# controller5.net
KiCad netlist of a schematic drawn in EAGLE
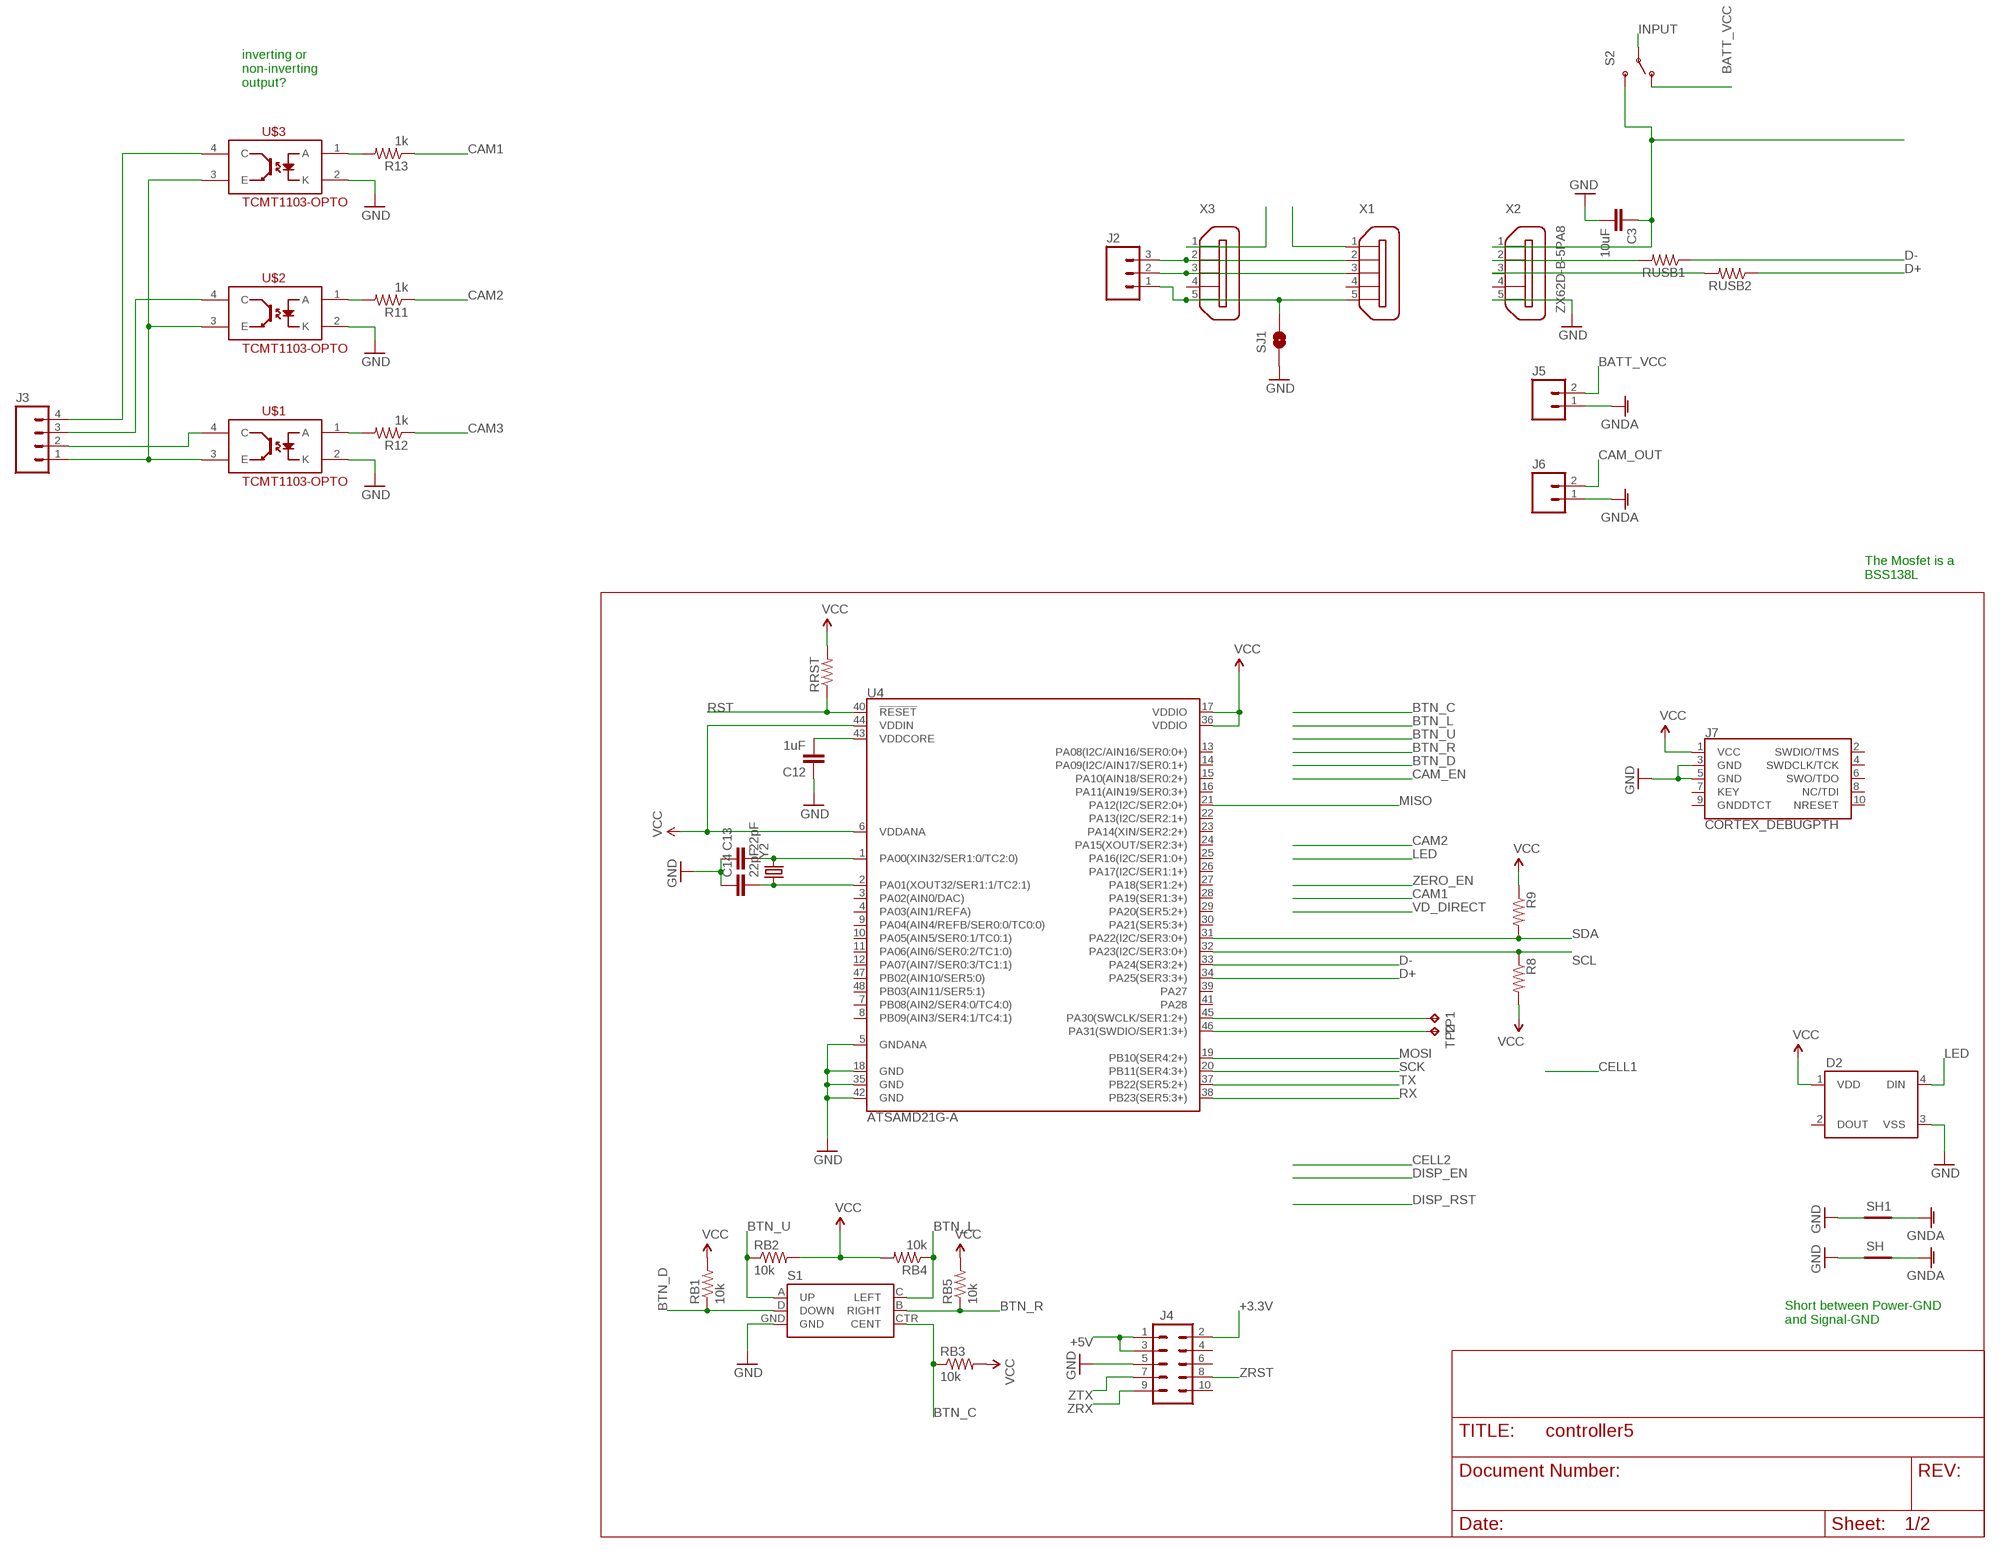
[diagram p0: schematic, sheet 1]
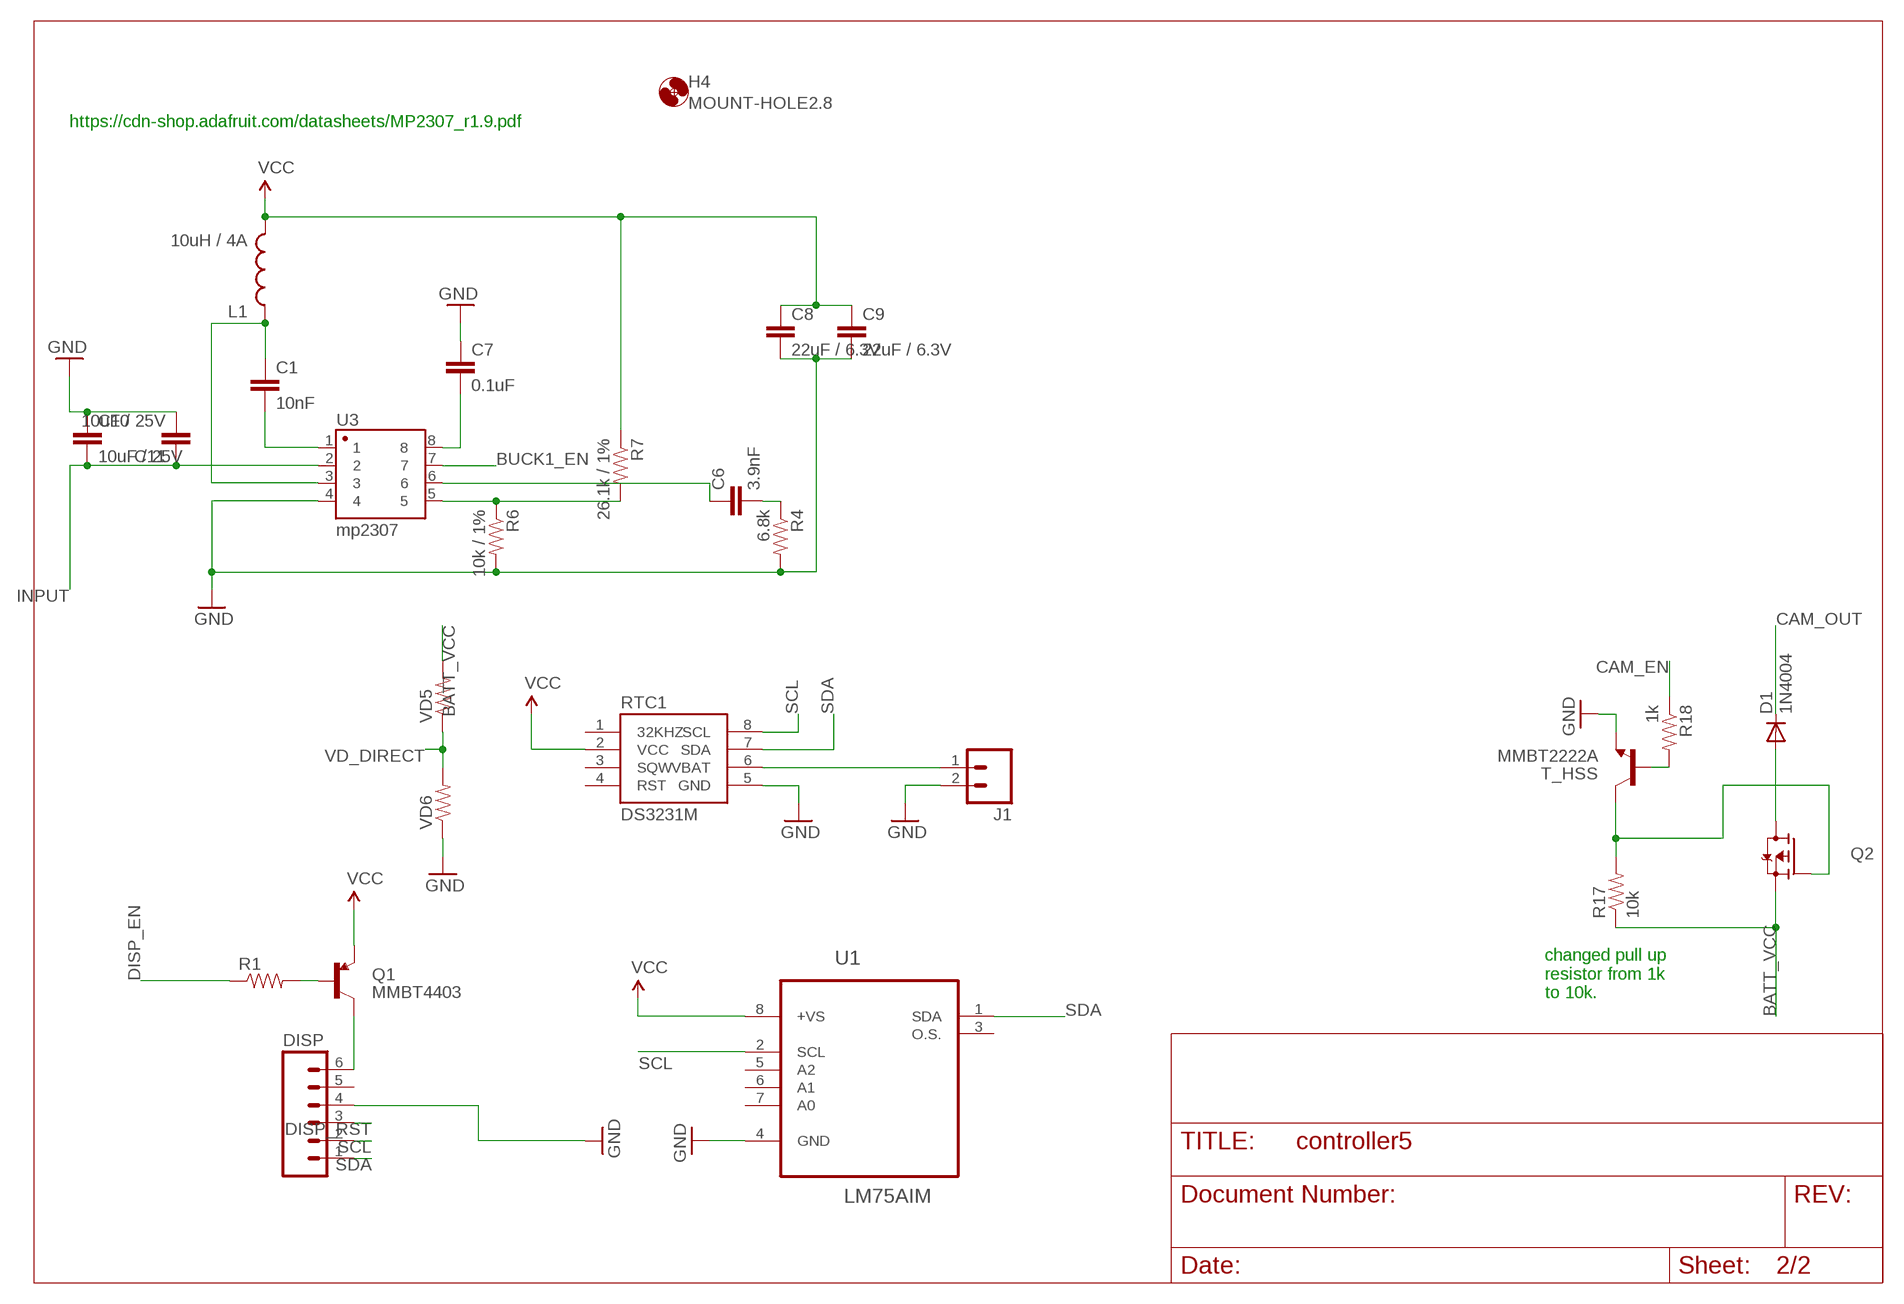
[diagram p1: schematic, sheet 2]

(export (version "E")
  (design (tool "Eeschema 10.0.6"))
  (components
    (comp (ref "C1")
      (value "10nF")
      (footprint "eagle-import:1206")
      (libsource (lib "eagle-import") (part "CAP1206"))
    )
    (comp (ref "C6")
      (value "3.9nF")
      (footprint "eagle-import:1206")
      (libsource (lib "eagle-import") (part "CAP1206"))
    )
    (comp (ref "C7")
      (value "0.1uF")
      (footprint "eagle-import:1206")
      (libsource (lib "eagle-import") (part "CAP1206"))
    )
    (comp (ref "C8")
      (value "22uF / 6.3V")
      (footprint "eagle-import:1206")
      (libsource (lib "eagle-import") (part "CAP1206"))
    )
    (comp (ref "C9")
      (value "22uF / 6.3V")
      (footprint "eagle-import:1206")
      (libsource (lib "eagle-import") (part "CAP1206"))
    )
    (comp (ref "C10")
      (value "10uF / 25V")
      (footprint "eagle-import:1206")
      (libsource (lib "eagle-import") (part "CAP1206"))
    )
    (comp (ref "C11")
      (value "10uF / 25V")
      (footprint "eagle-import:1206")
      (libsource (lib "eagle-import") (part "CAP1206"))
    )
    (comp (ref "D1")
      (value "1N4004")
      (footprint "eagle-import:DO41-10")
      (libsource (lib "eagle-import") (part "1N4004"))
    )
    (comp (ref "DISP")
      (value "M06FEMALE_LOCK")
      (footprint "eagle-import:1X06_FEMALE_LOCK.010")
      (libsource (lib "eagle-import") (part "M06FEMALE_LOCK"))
    )
    (comp (ref "H4")
      (value "MOUNT-HOLE2.8")
      (footprint "eagle-import:2,8")
      (libsource (lib "eagle-import") (part "MOUNT-HOLE2.8"))
    )
    (comp (ref "J1")
      (value "M02LOCK_LONGPADS")
      (footprint "eagle-import:1X02_LOCK_LONGPADS")
      (libsource (lib "eagle-import") (part "M02LOCK_LONGPADS"))
    )
    (comp (ref "L1")
      (value "10uH / 4A")
      (footprint "eagle-import:SDR0403")
      (libsource (lib "eagle-import") (part "INDUCTORSDR0403-560KL"))
    )
    (comp (ref "Q1")
      (value "MMBT4403")
      (footprint "eagle-import:SOT23-3")
      (libsource (lib "eagle-import") (part "TRANSISTOR_PNPMMBT4403"))
    )
    (comp (ref "Q2")
      (value "FDD4141TO252")
      (footprint "eagle-import:TO252")
      (libsource (lib "eagle-import") (part "FDD4141TO252"))
    )
    (comp (ref "R1")
      (value "RESISTOR1206")
      (footprint "eagle-import:1206")
      (libsource (lib "eagle-import") (part "SparkFun-Resistors_RESISTOR1206"))
    )
    (comp (ref "R4")
      (value "6.8k")
      (footprint "eagle-import:1206")
      (libsource (lib "eagle-import") (part "SparkFun-Resistors_RESISTOR1206"))
    )
    (comp (ref "R6")
      (value "10k / 1%")
      (footprint "eagle-import:1206")
      (libsource (lib "eagle-import") (part "SparkFun-Resistors_RESISTOR1206"))
    )
    (comp (ref "R7")
      (value "26.1k / 1%")
      (footprint "eagle-import:1206")
      (libsource (lib "eagle-import") (part "SparkFun-Resistors_RESISTOR1206"))
    )
    (comp (ref "R17")
      (value "10k")
      (footprint "eagle-import:1206")
      (libsource (lib "eagle-import") (part "SparkFun-Resistors_RESISTOR1206"))
    )
    (comp (ref "R18")
      (value "1k")
      (footprint "eagle-import:1206")
      (libsource (lib "eagle-import") (part "SparkFun-Resistors_RESISTOR1206"))
    )
    (comp (ref "RTC1")
      (value "DS3231M")
      (footprint "eagle-import:SOIC8")
      (libsource (lib "eagle-import") (part "DS3231M"))
    )
    (comp (ref "T_HSS")
      (value "MMBT2222A")
      (footprint "eagle-import:SOT23-3")
      (libsource (lib "eagle-import") (part "TRANSISTOR_NPNMMBT2222A"))
    )
    (comp (ref "U1")
      (value "LM75AIM")
      (footprint "eagle-import:SOIC127P620X175-8N")
      (libsource (lib "eagle-import") (part "LM75AIM"))
    )
    (comp (ref "U3")
      (value "mp2307")
      (footprint "eagle-import:SO08-UNIVERSAL")
      (libsource (lib "eagle-import") (part "GENERIC-SOIC8"))
    )
    (comp (ref "VD5")
      (value "RESISTOR1206")
      (footprint "eagle-import:1206")
      (libsource (lib "eagle-import") (part "RESISTOR1206"))
    )
    (comp (ref "VD6")
      (value "RESISTOR1206")
      (footprint "eagle-import:1206")
      (libsource (lib "eagle-import") (part "RESISTOR1206"))
    )
    (comp (ref "C3")
      (value "10uF")
      (footprint "eagle-import:1206")
      (libsource (lib "eagle-import") (part "SparkFun-Passives_CAP1206"))
    )
    (comp (ref "C12")
      (value "1uF")
      (footprint "eagle-import:1206")
      (libsource (lib "eagle-import") (part "CAP1206"))
    )
    (comp (ref "C13")
      (value "22pF")
      (footprint "eagle-import:1206")
      (libsource (lib "eagle-import") (part "SparkFun-Passives_CAP1206"))
    )
    (comp (ref "C14")
      (value "22pF")
      (footprint "eagle-import:1206")
      (libsource (lib "eagle-import") (part "SparkFun-Passives_CAP1206"))
    )
    (comp (ref "D2")
      (value "WS2812B")
      (footprint "eagle-import:WS2812B")
      (libsource (lib "eagle-import") (part "WS2812B"))
    )
    (comp (ref "J2")
      (value "M03LOCK")
      (footprint "eagle-import:1X03_LOCK")
      (libsource (lib "eagle-import") (part "M03LOCK"))
    )
    (comp (ref "J3")
      (value "M04LOCK")
      (footprint "eagle-import:1X04_LOCK")
      (libsource (lib "eagle-import") (part "M04LOCK"))
    )
    (comp (ref "J4")
      (value "M05X2NO_SILK")
      (footprint "eagle-import:2X5_NOSILK")
      (libsource (lib "eagle-import") (part "M05X2NO_SILK"))
    )
    (comp (ref "J5")
      (value "M023.5MM_LOCK")
      (footprint "eagle-import:SCREWTERMINAL-3.5MM-2_LOCK")
      (libsource (lib "eagle-import") (part "M023.5MM_LOCK"))
    )
    (comp (ref "J6")
      (value "M023.5MM_LOCK")
      (footprint "eagle-import:SCREWTERMINAL-3.5MM-2_LOCK")
      (libsource (lib "eagle-import") (part "M023.5MM_LOCK"))
    )
    (comp (ref "J7")
      (value "CORTEX_DEBUGPTH")
      (footprint "eagle-import:2X5-PTH-1.27MM")
      (libsource (lib "eagle-import") (part "CORTEX_DEBUGPTH"))
    )
    (comp (ref "R8")
      (value "RESISTOR1206")
      (footprint "eagle-import:1206")
      (libsource (lib "eagle-import") (part "RESISTOR1206"))
    )
    (comp (ref "R9")
      (value "RESISTOR1206")
      (footprint "eagle-import:1206")
      (libsource (lib "eagle-import") (part "RESISTOR1206"))
    )
    (comp (ref "R11")
      (value "1k")
      (footprint "eagle-import:1206")
      (libsource (lib "eagle-import") (part "SparkFun-Resistors_RESISTOR1206"))
    )
    (comp (ref "R12")
      (value "1k")
      (footprint "eagle-import:1206")
      (libsource (lib "eagle-import") (part "SparkFun-Resistors_RESISTOR1206"))
    )
    (comp (ref "R13")
      (value "1k")
      (footprint "eagle-import:1206")
      (libsource (lib "eagle-import") (part "SparkFun-Resistors_RESISTOR1206"))
    )
    (comp (ref "RB1")
      (value "10k")
      (footprint "eagle-import:1206")
      (libsource (lib "eagle-import") (part "SparkFun-Resistors_RESISTOR1206"))
    )
    (comp (ref "RB2")
      (value "10k")
      (footprint "eagle-import:1206")
      (libsource (lib "eagle-import") (part "SparkFun-Resistors_RESISTOR1206"))
    )
    (comp (ref "RB3")
      (value "10k")
      (footprint "eagle-import:1206")
      (libsource (lib "eagle-import") (part "SparkFun-Resistors_RESISTOR1206"))
    )
    (comp (ref "RB4")
      (value "10k")
      (footprint "eagle-import:1206")
      (libsource (lib "eagle-import") (part "SparkFun-Resistors_RESISTOR1206"))
    )
    (comp (ref "RB5")
      (value "10k")
      (footprint "eagle-import:1206")
      (libsource (lib "eagle-import") (part "SparkFun-Resistors_RESISTOR1206"))
    )
    (comp (ref "RRST")
      (value "RESISTOR1206")
      (footprint "eagle-import:1206")
      (libsource (lib "eagle-import") (part "RESISTOR1206"))
    )
    (comp (ref "RUSB1")
      (value "RESISTOR1206")
      (footprint "eagle-import:1206")
      (libsource (lib "eagle-import") (part "RESISTOR1206"))
    )
    (comp (ref "RUSB2")
      (value "RESISTOR1206")
      (footprint "eagle-import:1206")
      (libsource (lib "eagle-import") (part "RESISTOR1206"))
    )
    (comp (ref "S1")
      (value "JOYSTICK_MINI")
      (footprint "eagle-import:JOYSTICK_MINI")
      (libsource (lib "eagle-import") (part "JOYSTICK_MINI"))
    )
    (comp (ref "S2")
      (value "SWITCH-SPDTPTH_LOCK")
      (footprint "eagle-import:SWITCH-SPDT_LOCK.007S")
      (libsource (lib "eagle-import") (part "SWITCH-SPDTPTH_LOCK"))
    )
    (comp (ref "SH")
      (value "SHORT-HT5")
      (footprint "eagle-import:SHORT_TOP-50")
      (libsource (lib "eagle-import") (part "SHORT-HT5"))
    )
    (comp (ref "SH1")
      (value "SHORT-HT5")
      (footprint "eagle-import:SHORT_TOP-50")
      (libsource (lib "eagle-import") (part "SHORT-HT5"))
    )
    (comp (ref "SJ1")
      (value "SOLDERJUMPERNO")
      (footprint "eagle-import:SJ_2S-NO")
      (libsource (lib "eagle-import") (part "SOLDERJUMPERNO"))
    )
    (comp (ref "TP1")
      (value "TPTP20R")
      (footprint "eagle-import:TP20R")
      (libsource (lib "eagle-import") (part "TPTP20R"))
    )
    (comp (ref "TP2")
      (value "TPTP20R")
      (footprint "eagle-import:TP20R")
      (libsource (lib "eagle-import") (part "TPTP20R"))
    )
    (comp (ref "U$1")
      (value "TCMT1103-OPTO")
      (footprint "eagle-import:SSOP-4")
      (libsource (lib "eagle-import") (part "TCMT1103-OPTO"))
    )
    (comp (ref "U$2")
      (value "TCMT1103-OPTO")
      (footprint "eagle-import:SSOP-4")
      (libsource (lib "eagle-import") (part "TCMT1103-OPTO"))
    )
    (comp (ref "U$3")
      (value "TCMT1103-OPTO")
      (footprint "eagle-import:SSOP-4")
      (libsource (lib "eagle-import") (part "TCMT1103-OPTO"))
    )
    (comp (ref "U4")
      (value "ATSAMD21G-A")
      (footprint "eagle-import:TQFP-48")
      (libsource (lib "eagle-import") (part "ATSAMD21G-A"))
    )
    (comp (ref "X1")
      (value "ZX62D-B-5PA8")
      (footprint "eagle-import:ZX62D-B-5PA8")
      (fields (field (name "MF") "Hirose"))
      (libsource (lib "eagle-import") (part "ZX62D-B-5PA8"))
    )
    (comp (ref "X2")
      (value "ZX62D-B-5PA8")
      (footprint "eagle-import:ZX62D-B-5PA8")
      (fields (field (name "MF") "Hirose"))
      (libsource (lib "eagle-import") (part "ZX62D-B-5PA8"))
    )
    (comp (ref "X3")
      (value "ZX62D-B-5PA8")
      (footprint "eagle-import:ZX62D-B-5PA8")
      (fields (field (name "MF") "Hirose"))
      (libsource (lib "eagle-import") (part "ZX62D-B-5PA8"))
    )
    (comp (ref "Y2")
      (value "CRYSTALCRYSTAL-SMD-5X3-16MHZ")
      (footprint "eagle-import:CRYSTAL-SMD-5X3")
      (libsource (lib "eagle-import") (part "CRYSTALCRYSTAL-SMD-5X3-16MHZ"))
    )
  )
  (nets
    (net (code "1") (name "+3.3V") (class "Default")
      (node (ref "J4") (pin "2") (pinfunction "2_2") (pintype "passive"))
    )
    (net (code "2") (name "+5V") (class "Default")
      (node (ref "J4") (pin "1") (pinfunction "1_1") (pintype "passive"))
      (node (ref "J4") (pin "3") (pinfunction "3_3") (pintype "passive"))
    )
    (net (code "3") (name "BATT_VCC") (class "Default")
      (node (ref "J5") (pin "2") (pinfunction "2_2") (pintype "passive"))
      (node (ref "Q2") (pin "2") (pinfunction "S_2") (pintype "passive"))
      (node (ref "R17") (pin "1") (pinfunction "1_1") (pintype "passive"))
      (node (ref "S2") (pin "1") (pinfunction "O_1") (pintype "passive"))
      (node (ref "VD5") (pin "2") (pinfunction "2_2") (pintype "passive"))
    )
    (net (code "4") (name "BTN_C") (class "Default")
      (node (ref "RB3") (pin "1") (pinfunction "1_1") (pintype "passive"))
      (node (ref "S1") (pin "CTR") (pinfunction "CENT_CTR") (pintype "bidirectional"))
    )
    (net (code "5") (name "BTN_D") (class "Default")
      (node (ref "RB1") (pin "1") (pinfunction "1_1") (pintype "passive"))
      (node (ref "S1") (pin "D") (pinfunction "DOWN_D") (pintype "bidirectional"))
    )
    (net (code "6") (name "BTN_L") (class "Default")
      (node (ref "RB4") (pin "1") (pinfunction "1_1") (pintype "passive"))
      (node (ref "S1") (pin "C") (pinfunction "LEFT_C") (pintype "bidirectional"))
    )
    (net (code "7") (name "BTN_R") (class "Default")
      (node (ref "RB5") (pin "1") (pinfunction "1_1") (pintype "passive"))
      (node (ref "S1") (pin "B") (pinfunction "RIGHT_B") (pintype "bidirectional"))
    )
    (net (code "8") (name "BTN_U") (class "Default")
      (node (ref "RB2") (pin "1") (pinfunction "1_1") (pintype "passive"))
      (node (ref "S1") (pin "A") (pinfunction "UP_A") (pintype "bidirectional"))
    )
    (net (code "9") (name "BUCK1_EN") (class "Default")
      (node (ref "U3") (pin "7") (pinfunction "7_7") (pintype "bidirectional"))
    )
    (net (code "10") (name "CAM1") (class "Default")
      (node (ref "R13") (pin "1") (pinfunction "1_1") (pintype "passive"))
    )
    (net (code "11") (name "CAM2") (class "Default")
      (node (ref "R11") (pin "1") (pinfunction "1_1") (pintype "passive"))
    )
    (net (code "12") (name "CAM3") (class "Default")
      (node (ref "R12") (pin "1") (pinfunction "1_1") (pintype "passive"))
    )
    (net (code "13") (name "CAM_EN") (class "Default")
      (node (ref "R18") (pin "1") (pinfunction "1_1") (pintype "passive"))
    )
    (net (code "14") (name "CAM_OUT") (class "Default")
      (node (ref "D1") (pin "C") (pinfunction "C_C") (pintype "passive"))
      (node (ref "J6") (pin "2") (pinfunction "2_2") (pintype "passive"))
    )
    (net (code "17") (name "D+") (class "Default")
      (node (ref "RUSB2") (pin "1") (pinfunction "1_1") (pintype "passive"))
      (node (ref "U4") (pin "34") (pinfunction "PA25(SER3:3+)_34") (pintype "bidirectional"))
    )
    (net (code "18") (name "D-") (class "Default")
      (node (ref "RUSB1") (pin "1") (pinfunction "1_1") (pintype "passive"))
      (node (ref "U4") (pin "33") (pinfunction "PA24(SER3:2+)_33") (pintype "bidirectional"))
    )
    (net (code "19") (name "DISP_EN") (class "Default")
      (node (ref "R1") (pin "1") (pinfunction "1_1") (pintype "passive"))
    )
    (net (code "20") (name "DISP_RST") (class "Default")
      (node (ref "DISP") (pin "3") (pinfunction "3_3") (pintype "passive"))
    )
    (net (code "21") (name "GND") (class "Default")
      (node (ref "C10") (pin "1") (pinfunction "1_1") (pintype "passive"))
      (node (ref "C11") (pin "2") (pinfunction "2_2") (pintype "passive"))
      (node (ref "C12") (pin "1") (pinfunction "1_1") (pintype "passive"))
      (node (ref "C13") (pin "1") (pinfunction "1_1") (pintype "passive"))
      (node (ref "C14") (pin "1") (pinfunction "1_1") (pintype "passive"))
      (node (ref "C3") (pin "2") (pinfunction "2_2") (pintype "passive"))
      (node (ref "C7") (pin "1") (pinfunction "1_1") (pintype "passive"))
      (node (ref "C8") (pin "2") (pinfunction "2_2") (pintype "passive"))
      (node (ref "C9") (pin "2") (pinfunction "2_2") (pintype "passive"))
      (node (ref "D2") (pin "3") (pinfunction "VSS_3") (pintype "power_in"))
      (node (ref "DISP") (pin "4") (pinfunction "4_4") (pintype "passive"))
      (node (ref "J1") (pin "2") (pinfunction "2_2") (pintype "passive"))
      (node (ref "J4") (pin "5") (pinfunction "5_5") (pintype "passive"))
      (node (ref "J7") (pin "3") (pinfunction "GND_3") (pintype "bidirectional"))
      (node (ref "J7") (pin "5") (pinfunction "GND_5") (pintype "bidirectional"))
      (node (ref "R4") (pin "2") (pinfunction "2_2") (pintype "passive"))
      (node (ref "R6") (pin "2") (pinfunction "2_2") (pintype "passive"))
      (node (ref "RTC1") (pin "5") (pinfunction "GND_5") (pintype "power_in"))
      (node (ref "S1") (pin "GND") (pinfunction "GND_GND") (pintype "bidirectional"))
      (node (ref "SH") (pin "1") (pinfunction "P$1_1") (pintype "bidirectional"))
      (node (ref "SH1") (pin "1") (pinfunction "P$1_1") (pintype "bidirectional"))
      (node (ref "SJ1") (pin "1") (pinfunction "1_1") (pintype "passive"))
      (node (ref "T_HSS") (pin "2") (pinfunction "E_2") (pintype "passive"))
      (node (ref "U$1") (pin "2") (pinfunction "K_2") (pintype "bidirectional"))
      (node (ref "U$2") (pin "2") (pinfunction "K_2") (pintype "bidirectional"))
      (node (ref "U$3") (pin "2") (pinfunction "K_2") (pintype "bidirectional"))
      (node (ref "U1") (pin "4") (pinfunction "GND_4") (pintype "passive"))
      (node (ref "U3") (pin "4") (pinfunction "4_4") (pintype "bidirectional"))
      (node (ref "U4") (pin "18") (pinfunction "GND_18") (pintype "bidirectional"))
      (node (ref "U4") (pin "35") (pinfunction "GND_35") (pintype "bidirectional"))
      (node (ref "U4") (pin "42") (pinfunction "GND_42") (pintype "bidirectional"))
      (node (ref "U4") (pin "5") (pinfunction "GNDANA_5") (pintype "bidirectional"))
      (node (ref "VD6") (pin "1") (pinfunction "1_1") (pintype "passive"))
      (node (ref "X2") (pin "5") (pinfunction "5_5") (pintype "passive"))
    )
    (net (code "22") (name "GNDA") (class "Default")
      (node (ref "J5") (pin "1") (pinfunction "1_1") (pintype "passive"))
      (node (ref "J6") (pin "1") (pinfunction "1_1") (pintype "passive"))
      (node (ref "SH") (pin "2") (pinfunction "P$2_2") (pintype "bidirectional"))
      (node (ref "SH1") (pin "2") (pinfunction "P$2_2") (pintype "bidirectional"))
    )
    (net (code "23") (name "INPUT") (class "Default")
      (node (ref "C10") (pin "2") (pinfunction "2_2") (pintype "passive"))
      (node (ref "C11") (pin "1") (pinfunction "1_1") (pintype "passive"))
      (node (ref "S2") (pin "2") (pinfunction "P_2") (pintype "passive"))
      (node (ref "U3") (pin "2") (pinfunction "2_2") (pintype "bidirectional"))
    )
    (net (code "24") (name "LED") (class "Default")
      (node (ref "D2") (pin "4") (pinfunction "DIN_4") (pintype "input"))
    )
    (net (code "25") (name "MISO") (class "Default")
      (node (ref "U4") (pin "21") (pinfunction "PA12(I2C/SER2:0+)_21") (pintype "bidirectional"))
    )
    (net (code "26") (name "MOSI") (class "Default")
      (node (ref "U4") (pin "19") (pinfunction "PB10(SER4:2+)_19") (pintype "bidirectional"))
    )
    (net (code "27") (name "Net-(C1-Pad2)") (class "Default")
      (node (ref "C1") (pin "2") (pinfunction "2_2") (pintype "passive"))
      (node (ref "U3") (pin "1") (pinfunction "1_1") (pintype "bidirectional"))
    )
    (net (code "28") (name "Net-(C6-Pad1)") (class "Default")
      (node (ref "C6") (pin "1") (pinfunction "1_1") (pintype "passive"))
      (node (ref "U3") (pin "6") (pinfunction "6_6") (pintype "bidirectional"))
    )
    (net (code "29") (name "Net-(C6-Pad2)") (class "Default")
      (node (ref "C6") (pin "2") (pinfunction "2_2") (pintype "passive"))
      (node (ref "R4") (pin "1") (pinfunction "1_1") (pintype "passive"))
    )
    (net (code "30") (name "Net-(C7-Pad2)") (class "Default")
      (node (ref "C7") (pin "2") (pinfunction "2_2") (pintype "passive"))
      (node (ref "U3") (pin "8") (pinfunction "8_8") (pintype "bidirectional"))
    )
    (net (code "31") (name "Net-(J2-Pad1)") (class "Default")
      (node (ref "J2") (pin "1") (pinfunction "1_1") (pintype "passive"))
      (node (ref "SJ1") (pin "2") (pinfunction "2_2") (pintype "passive"))
      (node (ref "X1") (pin "5") (pinfunction "5_5") (pintype "passive"))
      (node (ref "X3") (pin "5") (pinfunction "5_5") (pintype "passive"))
    )
    (net (code "32") (name "Net-(J2-Pad2)") (class "Default")
      (node (ref "J2") (pin "2") (pinfunction "2_2") (pintype "passive"))
      (node (ref "X1") (pin "3") (pinfunction "3_3") (pintype "passive"))
      (node (ref "X3") (pin "3") (pinfunction "3_3") (pintype "passive"))
    )
    (net (code "33") (name "Net-(J2-Pad3)") (class "Default")
      (node (ref "J2") (pin "3") (pinfunction "3_3") (pintype "passive"))
      (node (ref "X1") (pin "2") (pinfunction "2_2") (pintype "passive"))
      (node (ref "X3") (pin "2") (pinfunction "2_2") (pintype "passive"))
    )
    (net (code "34") (name "Net-(L1-1)") (class "Default")
      (node (ref "C1") (pin "1") (pinfunction "1_1") (pintype "passive"))
      (node (ref "L1") (pin "P$1") (pinfunction "1_P$1") (pintype "passive"))
      (node (ref "U3") (pin "3") (pinfunction "3_3") (pintype "bidirectional"))
    )
    (net (code "35") (name "Net-(Q1-B)") (class "Default")
      (node (ref "Q1") (pin "1") (pinfunction "B_1") (pintype "passive"))
      (node (ref "R1") (pin "2") (pinfunction "2_2") (pintype "passive"))
    )
    (net (code "36") (name "Net-(Q1-C)") (class "Default")
      (node (ref "DISP") (pin "6") (pinfunction "6_6") (pintype "passive"))
      (node (ref "Q1") (pin "3") (pinfunction "C_3") (pintype "passive"))
    )
    (net (code "37") (name "Net-(Q2-D)") (class "Default")
      (node (ref "D1") (pin "A") (pinfunction "A_A") (pintype "passive"))
      (node (ref "Q2") (pin "3") (pinfunction "D_3") (pintype "passive"))
    )
    (net (code "38") (name "Net-(Q2-G)") (class "Default")
      (node (ref "Q2") (pin "1") (pinfunction "G_1") (pintype "passive"))
      (node (ref "R17") (pin "2") (pinfunction "2_2") (pintype "passive"))
      (node (ref "T_HSS") (pin "3") (pinfunction "C_3") (pintype "passive"))
    )
    (net (code "39") (name "Net-(R6-Pad1)") (class "Default")
      (node (ref "R6") (pin "1") (pinfunction "1_1") (pintype "passive"))
      (node (ref "R7") (pin "2") (pinfunction "2_2") (pintype "passive"))
      (node (ref "U3") (pin "5") (pinfunction "5_5") (pintype "bidirectional"))
    )
    (net (code "40") (name "Net-(RTC1-VBAT)") (class "Default")
      (node (ref "J1") (pin "1") (pinfunction "1_1") (pintype "passive"))
      (node (ref "RTC1") (pin "6") (pinfunction "VBAT_6") (pintype "power_in"))
    )
    (net (code "41") (name "Net-(RUSB1-Pad2)") (class "Default")
      (node (ref "RUSB1") (pin "2") (pinfunction "2_2") (pintype "passive"))
      (node (ref "X2") (pin "2") (pinfunction "2_2") (pintype "passive"))
    )
    (net (code "42") (name "Net-(RUSB2-Pad2)") (class "Default")
      (node (ref "RUSB2") (pin "2") (pinfunction "2_2") (pintype "passive"))
      (node (ref "X2") (pin "3") (pinfunction "3_3") (pintype "passive"))
    )
    (net (code "43") (name "Net-(S2-S)") (class "Default")
      (node (ref "C3") (pin "1") (pinfunction "1_1") (pintype "passive"))
      (node (ref "S2") (pin "3") (pinfunction "S_3") (pintype "passive"))
      (node (ref "X2") (pin "1") (pinfunction "1_1") (pintype "passive"))
    )
    (net (code "44") (name "Net-(T_HSS-B)") (class "Default")
      (node (ref "R18") (pin "2") (pinfunction "2_2") (pintype "passive"))
      (node (ref "T_HSS") (pin "1") (pinfunction "B_1") (pintype "passive"))
    )
    (net (code "45") (name "Net-(U$1-A)") (class "Default")
      (node (ref "R12") (pin "2") (pinfunction "2_2") (pintype "passive"))
      (node (ref "U$1") (pin "1") (pinfunction "A_1") (pintype "bidirectional"))
    )
    (net (code "46") (name "Net-(U$1-C)") (class "Default")
      (node (ref "J3") (pin "2") (pinfunction "2_2") (pintype "passive"))
      (node (ref "U$1") (pin "4") (pinfunction "C_4") (pintype "bidirectional"))
    )
    (net (code "47") (name "Net-(U$1-E)") (class "Default")
      (node (ref "J3") (pin "1") (pinfunction "1_1") (pintype "passive"))
      (node (ref "U$1") (pin "3") (pinfunction "E_3") (pintype "bidirectional"))
      (node (ref "U$2") (pin "3") (pinfunction "E_3") (pintype "bidirectional"))
      (node (ref "U$3") (pin "3") (pinfunction "E_3") (pintype "bidirectional"))
    )
    (net (code "48") (name "Net-(U$2-A)") (class "Default")
      (node (ref "R11") (pin "2") (pinfunction "2_2") (pintype "passive"))
      (node (ref "U$2") (pin "1") (pinfunction "A_1") (pintype "bidirectional"))
    )
    (net (code "49") (name "Net-(U$2-C)") (class "Default")
      (node (ref "J3") (pin "3") (pinfunction "3_3") (pintype "passive"))
      (node (ref "U$2") (pin "4") (pinfunction "C_4") (pintype "bidirectional"))
    )
    (net (code "50") (name "Net-(U$3-A)") (class "Default")
      (node (ref "R13") (pin "2") (pinfunction "2_2") (pintype "passive"))
      (node (ref "U$3") (pin "1") (pinfunction "A_1") (pintype "bidirectional"))
    )
    (net (code "51") (name "Net-(U$3-C)") (class "Default")
      (node (ref "J3") (pin "4") (pinfunction "4_4") (pintype "passive"))
      (node (ref "U$3") (pin "4") (pinfunction "C_4") (pintype "bidirectional"))
    )
    (net (code "52") (name "Net-(U4-PA00(XIN32{slash}SER1:0{slash}TC2:0))") (class "Default")
      (node (ref "C13") (pin "2") (pinfunction "2_2") (pintype "passive"))
      (node (ref "U4") (pin "1") (pinfunction "PA00(XIN32/SER1:0/TC2:0)_1") (pintype "bidirectional"))
      (node (ref "Y2") (pin "3") (pinfunction "2_3") (pintype "passive"))
    )
    (net (code "53") (name "Net-(U4-PA01(XOUT32{slash}SER1:1{slash}TC2:1))") (class "Default")
      (node (ref "C14") (pin "2") (pinfunction "2_2") (pintype "passive"))
      (node (ref "U4") (pin "2") (pinfunction "PA01(XOUT32/SER1:1/TC2:1)_2") (pintype "bidirectional"))
      (node (ref "Y2") (pin "1") (pinfunction "1_1") (pintype "passive"))
    )
    (net (code "54") (name "Net-(U4-PA30(SWCLK{slash}SER1:2+))") (class "Default")
      (node (ref "TP1") (pin "TP") (pinfunction "TP_TP") (pintype "input"))
      (node (ref "U4") (pin "45") (pinfunction "PA30(SWCLK/SER1:2+)_45") (pintype "bidirectional"))
    )
    (net (code "55") (name "Net-(U4-PA31(SWDIO{slash}SER1:3+))") (class "Default")
      (node (ref "TP2") (pin "TP") (pinfunction "TP_TP") (pintype "input"))
      (node (ref "U4") (pin "46") (pinfunction "PA31(SWDIO/SER1:3+)_46") (pintype "bidirectional"))
    )
    (net (code "56") (name "Net-(U4-VDDCORE)") (class "Default")
      (node (ref "C12") (pin "2") (pinfunction "2_2") (pintype "passive"))
      (node (ref "U4") (pin "43") (pinfunction "VDDCORE_43") (pintype "bidirectional"))
    )
    (net (code "57") (name "RST") (class "Default")
      (node (ref "RRST") (pin "1") (pinfunction "1_1") (pintype "passive"))
      (node (ref "U4") (pin "40") (pinfunction "~{RESET}_40") (pintype "bidirectional"))
    )
    (net (code "58") (name "RX") (class "Default")
      (node (ref "U4") (pin "38") (pinfunction "PB23(SER5:3+)_38") (pintype "bidirectional"))
    )
    (net (code "59") (name "SCK") (class "Default")
      (node (ref "U4") (pin "20") (pinfunction "PB11(SER4:3+)_20") (pintype "bidirectional"))
    )
    (net (code "60") (name "SCL") (class "Default")
      (node (ref "DISP") (pin "2") (pinfunction "2_2") (pintype "passive"))
      (node (ref "R8") (pin "1") (pinfunction "1_1") (pintype "passive"))
      (node (ref "RTC1") (pin "8") (pinfunction "SCL_8") (pintype "bidirectional"))
      (node (ref "U1") (pin "2") (pinfunction "SCL_2") (pintype "input"))
      (node (ref "U4") (pin "32") (pinfunction "PA23(I2C/SER3:0+)_32") (pintype "bidirectional"))
    )
    (net (code "61") (name "SDA") (class "Default")
      (node (ref "DISP") (pin "1") (pinfunction "1_1") (pintype "passive"))
      (node (ref "R9") (pin "2") (pinfunction "2_2") (pintype "passive"))
      (node (ref "RTC1") (pin "7") (pinfunction "SDA_7") (pintype "bidirectional"))
      (node (ref "U1") (pin "1") (pinfunction "SDA_1") (pintype "bidirectional"))
      (node (ref "U4") (pin "31") (pinfunction "PA22(I2C/SER3:0+)_31") (pintype "bidirectional"))
    )
    (net (code "62") (name "TX") (class "Default")
      (node (ref "U4") (pin "37") (pinfunction "PB22(SER5:2+)_37") (pintype "bidirectional"))
    )
    (net (code "63") (name "VCC") (class "Default")
      (node (ref "C8") (pin "1") (pinfunction "1_1") (pintype "passive"))
      (node (ref "C9") (pin "1") (pinfunction "1_1") (pintype "passive"))
      (node (ref "D2") (pin "1") (pinfunction "VDD_1") (pintype "power_in"))
      (node (ref "J7") (pin "1") (pinfunction "VCC_1") (pintype "bidirectional"))
      (node (ref "L1") (pin "P$2") (pinfunction "2_P$2") (pintype "passive"))
      (node (ref "Q1") (pin "2") (pinfunction "E_2") (pintype "passive"))
      (node (ref "R7") (pin "1") (pinfunction "1_1") (pintype "passive"))
      (node (ref "R8") (pin "2") (pinfunction "2_2") (pintype "passive"))
      (node (ref "R9") (pin "1") (pinfunction "1_1") (pintype "passive"))
      (node (ref "RB1") (pin "2") (pinfunction "2_2") (pintype "passive"))
      (node (ref "RB2") (pin "2") (pinfunction "2_2") (pintype "passive"))
      (node (ref "RB3") (pin "2") (pinfunction "2_2") (pintype "passive"))
      (node (ref "RB4") (pin "2") (pinfunction "2_2") (pintype "passive"))
      (node (ref "RB5") (pin "2") (pinfunction "2_2") (pintype "passive"))
      (node (ref "RRST") (pin "2") (pinfunction "2_2") (pintype "passive"))
      (node (ref "RTC1") (pin "2") (pinfunction "VCC_2") (pintype "power_in"))
      (node (ref "U1") (pin "8") (pinfunction "+VS_8") (pintype "power_in"))
      (node (ref "U4") (pin "17") (pinfunction "VDDIO_17") (pintype "bidirectional"))
      (node (ref "U4") (pin "36") (pinfunction "VDDIO_36") (pintype "bidirectional"))
      (node (ref "U4") (pin "44") (pinfunction "VDDIN_44") (pintype "bidirectional"))
      (node (ref "U4") (pin "6") (pinfunction "VDDANA_6") (pintype "bidirectional"))
    )
    (net (code "64") (name "VD_DIRECT") (class "Default")
      (node (ref "VD5") (pin "1") (pinfunction "1_1") (pintype "passive"))
      (node (ref "VD6") (pin "2") (pinfunction "2_2") (pintype "passive"))
    )
    (net (code "66") (name "ZRST") (class "Default")
      (node (ref "J4") (pin "8") (pinfunction "8_8") (pintype "passive"))
    )
    (net (code "67") (name "ZRX") (class "Default")
      (node (ref "J4") (pin "9") (pinfunction "9_9") (pintype "passive"))
    )
    (net (code "68") (name "ZTX") (class "Default")
      (node (ref "J4") (pin "7") (pinfunction "7_7") (pintype "passive"))
    )
    (net (code "69") (name "unconnected-(D2-DOUT-Pad2)") (class "Default")
      (node (ref "D2") (pin "2") (pinfunction "DOUT_2") (pintype "output"))
    )
    (net (code "70") (name "unconnected-(DISP-Pad5)") (class "Default")
      (node (ref "DISP") (pin "5") (pinfunction "5_5") (pintype "passive"))
    )
    (net (code "71") (name "unconnected-(J4-Pad4)") (class "Default")
      (node (ref "J4") (pin "4") (pinfunction "4_4") (pintype "passive"))
    )
    (net (code "72") (name "unconnected-(J4-Pad6)") (class "Default")
      (node (ref "J4") (pin "6") (pinfunction "6_6") (pintype "passive"))
    )
    (net (code "73") (name "unconnected-(J4-Pad10)") (class "Default")
      (node (ref "J4") (pin "10") (pinfunction "10_10") (pintype "passive"))
    )
    (net (code "74") (name "unconnected-(J7-GNDDTCT-Pad9)") (class "Default")
      (node (ref "J7") (pin "9") (pinfunction "GNDDTCT_9") (pintype "bidirectional"))
    )
    (net (code "75") (name "unconnected-(J7-KEY-Pad7)") (class "Default")
      (node (ref "J7") (pin "7") (pinfunction "KEY_7") (pintype "bidirectional"))
    )
    (net (code "76") (name "unconnected-(J7-NC{slash}TDI-Pad8)") (class "Default")
      (node (ref "J7") (pin "8") (pinfunction "NC/TDI_8") (pintype "bidirectional"))
    )
    (net (code "77") (name "unconnected-(J7-NRESET-Pad10)") (class "Default")
      (node (ref "J7") (pin "10") (pinfunction "NRESET_10") (pintype "bidirectional"))
    )
    (net (code "78") (name "unconnected-(J7-SWDCLK{slash}TCK-Pad4)") (class "Default")
      (node (ref "J7") (pin "4") (pinfunction "SWDCLK/TCK_4") (pintype "bidirectional"))
    )
    (net (code "79") (name "unconnected-(J7-SWDIO{slash}TMS-Pad2)") (class "Default")
      (node (ref "J7") (pin "2") (pinfunction "SWDIO/TMS_2") (pintype "bidirectional"))
    )
    (net (code "80") (name "unconnected-(J7-SWO{slash}TDO-Pad6)") (class "Default")
      (node (ref "J7") (pin "6") (pinfunction "SWO/TDO_6") (pintype "bidirectional"))
    )
    (net (code "81") (name "unconnected-(RTC1-32KHZ-Pad1)") (class "Default")
      (node (ref "RTC1") (pin "1") (pinfunction "32KHZ_1") (pintype "output"))
    )
    (net (code "82") (name "unconnected-(RTC1-RST-Pad4)") (class "Default")
      (node (ref "RTC1") (pin "4") (pinfunction "RST_4") (pintype "bidirectional"))
    )
    (net (code "83") (name "unconnected-(RTC1-SQW-Pad3)") (class "Default")
      (node (ref "RTC1") (pin "3") (pinfunction "SQW_3") (pintype "output"))
    )
    (net (code "84") (name "unconnected-(U1-A0-Pad7)") (class "Default")
      (node (ref "U1") (pin "7") (pinfunction "A0_7") (pintype "input"))
    )
    (net (code "85") (name "unconnected-(U1-A1-Pad6)") (class "Default")
      (node (ref "U1") (pin "6") (pinfunction "A1_6") (pintype "input"))
    )
    (net (code "86") (name "unconnected-(U1-A2-Pad5)") (class "Default")
      (node (ref "U1") (pin "5") (pinfunction "A2_5") (pintype "input"))
    )
    (net (code "87") (name "unconnected-(U1-O.S.-Pad3)") (class "Default")
      (node (ref "U1") (pin "3") (pinfunction "O.S._3") (pintype "output"))
    )
    (net (code "88") (name "unconnected-(U4-PA02(AIN0{slash}DAC)-Pad3)") (class "Default")
      (node (ref "U4") (pin "3") (pinfunction "PA02(AIN0/DAC)_3") (pintype "bidirectional"))
    )
    (net (code "89") (name "unconnected-(U4-PA03(AIN1{slash}REFA)-Pad4)") (class "Default")
      (node (ref "U4") (pin "4") (pinfunction "PA03(AIN1/REFA)_4") (pintype "bidirectional"))
    )
    (net (code "90") (name "unconnected-(U4-PA04(AIN4{slash}REFB{slash}SER0:0{slash}TC0:0)-Pad9)") (class "Default")
      (node (ref "U4") (pin "9") (pinfunction "PA04(AIN4/REFB/SER0:0/TC0:0)_9") (pintype "bidirectional"))
    )
    (net (code "91") (name "unconnected-(U4-PA05(AIN5{slash}SER0:1{slash}TC0:1)-Pad10)") (class "Default")
      (node (ref "U4") (pin "10") (pinfunction "PA05(AIN5/SER0:1/TC0:1)_10") (pintype "bidirectional"))
    )
    (net (code "92") (name "unconnected-(U4-PA06(AIN6{slash}SER0:2{slash}TC1:0)-Pad11)") (class "Default")
      (node (ref "U4") (pin "11") (pinfunction "PA06(AIN6/SER0:2/TC1:0)_11") (pintype "bidirectional"))
    )
    (net (code "93") (name "unconnected-(U4-PA07(AIN7{slash}SER0:3{slash}TC1:1)-Pad12)") (class "Default")
      (node (ref "U4") (pin "12") (pinfunction "PA07(AIN7/SER0:3/TC1:1)_12") (pintype "bidirectional"))
    )
    (net (code "94") (name "unconnected-(U4-PA08(I2C{slash}AIN16{slash}SER0:0+)-Pad13)") (class "Default")
      (node (ref "U4") (pin "13") (pinfunction "PA08(I2C/AIN16/SER0:0+)_13") (pintype "bidirectional"))
    )
    (net (code "95") (name "unconnected-(U4-PA09(I2C{slash}AIN17{slash}SER0:1+)-Pad14)") (class "Default")
      (node (ref "U4") (pin "14") (pinfunction "PA09(I2C/AIN17/SER0:1+)_14") (pintype "bidirectional"))
    )
    (net (code "96") (name "unconnected-(U4-PA10(AIN18{slash}SER0:2+)-Pad15)") (class "Default")
      (node (ref "U4") (pin "15") (pinfunction "PA10(AIN18/SER0:2+)_15") (pintype "bidirectional"))
    )
    (net (code "97") (name "unconnected-(U4-PA11(AIN19{slash}SER0:3+)-Pad16)") (class "Default")
      (node (ref "U4") (pin "16") (pinfunction "PA11(AIN19/SER0:3+)_16") (pintype "bidirectional"))
    )
    (net (code "98") (name "unconnected-(U4-PA13(I2C{slash}SER2:1+)-Pad22)") (class "Default")
      (node (ref "U4") (pin "22") (pinfunction "PA13(I2C/SER2:1+)_22") (pintype "bidirectional"))
    )
    (net (code "99") (name "unconnected-(U4-PA14(XIN{slash}SER2:2+)-Pad23)") (class "Default")
      (node (ref "U4") (pin "23") (pinfunction "PA14(XIN/SER2:2+)_23") (pintype "bidirectional"))
    )
    (net (code "100") (name "unconnected-(U4-PA15(XOUT{slash}SER2:3+)-Pad24)") (class "Default")
      (node (ref "U4") (pin "24") (pinfunction "PA15(XOUT/SER2:3+)_24") (pintype "bidirectional"))
    )
    (net (code "101") (name "unconnected-(U4-PA16(I2C{slash}SER1:0+)-Pad25)") (class "Default")
      (node (ref "U4") (pin "25") (pinfunction "PA16(I2C/SER1:0+)_25") (pintype "bidirectional"))
    )
    (net (code "102") (name "unconnected-(U4-PA17(I2C{slash}SER1:1+)-Pad26)") (class "Default")
      (node (ref "U4") (pin "26") (pinfunction "PA17(I2C/SER1:1+)_26") (pintype "bidirectional"))
    )
    (net (code "103") (name "unconnected-(U4-PA18(SER1:2+)-Pad27)") (class "Default")
      (node (ref "U4") (pin "27") (pinfunction "PA18(SER1:2+)_27") (pintype "bidirectional"))
    )
    (net (code "104") (name "unconnected-(U4-PA19(SER1:3+)-Pad28)") (class "Default")
      (node (ref "U4") (pin "28") (pinfunction "PA19(SER1:3+)_28") (pintype "bidirectional"))
    )
    (net (code "105") (name "unconnected-(U4-PA20(SER5:2+)-Pad29)") (class "Default")
      (node (ref "U4") (pin "29") (pinfunction "PA20(SER5:2+)_29") (pintype "bidirectional"))
    )
    (net (code "106") (name "unconnected-(U4-PA21(SER5:3+)-Pad30)") (class "Default")
      (node (ref "U4") (pin "30") (pinfunction "PA21(SER5:3+)_30") (pintype "bidirectional"))
    )
    (net (code "107") (name "unconnected-(U4-PA27-Pad39)") (class "Default")
      (node (ref "U4") (pin "39") (pinfunction "PA27_39") (pintype "bidirectional"))
    )
    (net (code "108") (name "unconnected-(U4-PA28-Pad41)") (class "Default")
      (node (ref "U4") (pin "41") (pinfunction "PA28_41") (pintype "bidirectional"))
    )
    (net (code "109") (name "unconnected-(U4-PB02(AIN10{slash}SER5:0)-Pad47)") (class "Default")
      (node (ref "U4") (pin "47") (pinfunction "PB02(AIN10/SER5:0)_47") (pintype "bidirectional"))
    )
    (net (code "110") (name "unconnected-(U4-PB03(AIN11{slash}SER5:1)-Pad48)") (class "Default")
      (node (ref "U4") (pin "48") (pinfunction "PB03(AIN11/SER5:1)_48") (pintype "bidirectional"))
    )
    (net (code "111") (name "unconnected-(U4-PB08(AIN2{slash}SER4:0{slash}TC4:0)-Pad7)") (class "Default")
      (node (ref "U4") (pin "7") (pinfunction "PB08(AIN2/SER4:0/TC4:0)_7") (pintype "bidirectional"))
    )
    (net (code "112") (name "unconnected-(U4-PB09(AIN3{slash}SER4:1{slash}TC4:1)-Pad8)") (class "Default")
      (node (ref "U4") (pin "8") (pinfunction "PB09(AIN3/SER4:1/TC4:1)_8") (pintype "bidirectional"))
    )
    (net (code "113") (name "unconnected-(X1-Pad1)") (class "Default")
      (node (ref "X1") (pin "1") (pinfunction "1_1") (pintype "passive"))
    )
    (net (code "114") (name "unconnected-(X1-Pad4)") (class "Default")
      (node (ref "X1") (pin "4") (pinfunction "4_4") (pintype "passive"))
    )
    (net (code "115") (name "unconnected-(X2-Pad4)") (class "Default")
      (node (ref "X2") (pin "4") (pinfunction "4_4") (pintype "passive"))
    )
    (net (code "116") (name "unconnected-(X3-Pad1)") (class "Default")
      (node (ref "X3") (pin "1") (pinfunction "1_1") (pintype "passive"))
    )
    (net (code "117") (name "unconnected-(X3-Pad4)") (class "Default")
      (node (ref "X3") (pin "4") (pinfunction "4_4") (pintype "passive"))
    )
  )
)
